# MainPDU_13VBuck.net
KiCad netlist of a schematic drawn in Altium Designer
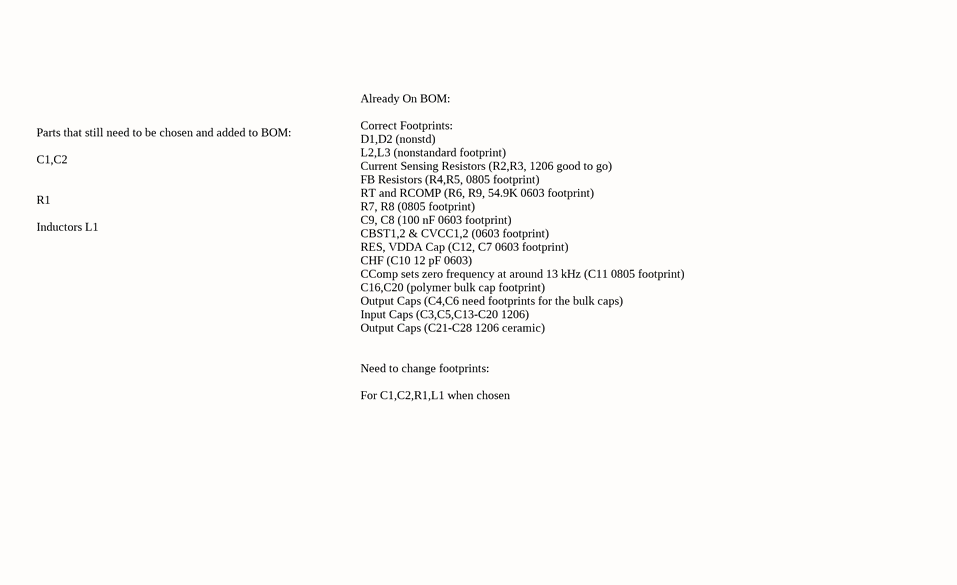
[diagram p0: MainPDU_13VBuck.SchDoc, left]
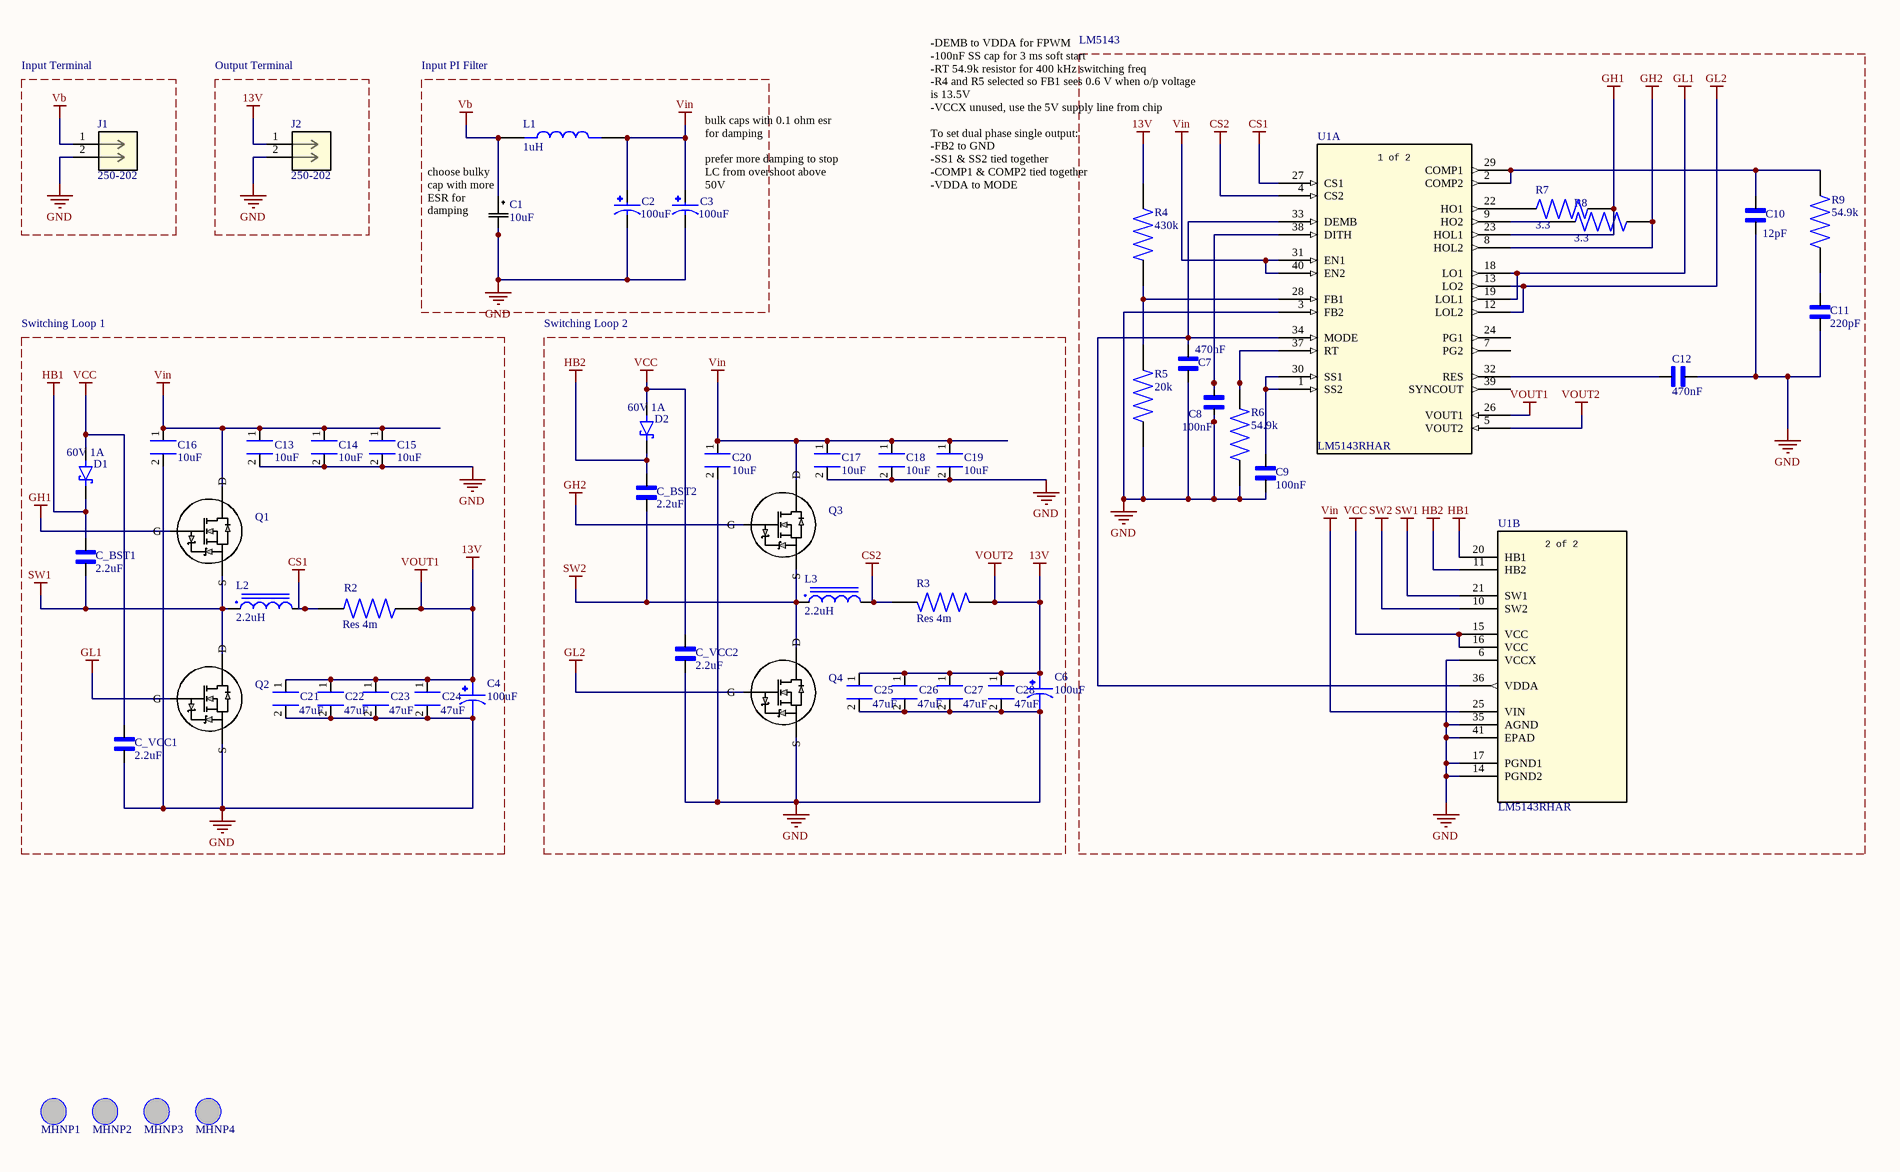
[diagram p1: MainPDU_13VBuck.SchDoc, right]

(export (version "E")
  (design (tool "Eeschema 10.0.6"))
  (components
    (comp (ref "C1")
      (value "10uF")
      (footprint "CAP_GY_6P3X5P8_NCH")
      (description "Description")
      (fields
        (field (name "MANUFACTURER_PART_NUMBER") "GYA1J100MCQ1GS")
        (field (name "COPYRIGHT") "Copyright (C) 2026 Ultra Librarian. All rights reserved.")
      )
      (libsource (lib "Schlib2") (part "GYA1J100MCQ1GS"))
    )
    (comp (ref "C2")
      (value "100uF")
      (footprint "CAP_YX_10X20_RUB")
      (description "Description")
      (fields
        (field (name "MANUFACTURER_PART_NUMBER") "100ZLH100MEFC10X20")
        (field (name "COPYRIGHT") "Copyright (C) 2025 Ultra Librarian. All rights reserved.")
      )
      (libsource (lib "Schlib2") (part "100ZLH100MEFC10X20"))
    )
    (comp (ref "C3")
      (value "100uF")
      (footprint "CAP_YX_10X20_RUB")
      (description "Description")
      (fields
        (field (name "MANUFACTURER_PART_NUMBER") "100ZLH100MEFC10X20")
        (field (name "COPYRIGHT") "Copyright (C) 2025 Ultra Librarian. All rights reserved.")
      )
      (libsource (lib "Schlib2") (part "100ZLH100MEFC10X20"))
    )
    (comp (ref "C4")
      (value "100uF")
      (footprint "CAPAE660X600N")
      (description "100 ÂµF 25 V Aluminum - Polymer Capacitors Radial, Can - SMD 36mOhm 2000 Hrs @ 125Â°C")
      (fields (field (name "MF") "KEMET") (field (name "MP") "A768EB107M1ELAS036"))
      (libsource (lib "Schlib2") (part "A768EB107M1ELAS036"))
    )
    (comp (ref "C6")
      (value "100uF")
      (footprint "CAPAE660X600N")
      (description "100 ÂµF 25 V Aluminum - Polymer Capacitors Radial, Can - SMD 36mOhm 2000 Hrs @ 125Â°C")
      (fields (field (name "MF") "KEMET") (field (name "MP") "A768EB107M1ELAS036"))
      (libsource (lib "Schlib2") (part "A768EB107M1ELAS036"))
    )
    (comp (ref "C7")
      (value "470nF")
      (footprint "CAPC1608X90N")
      (description "0.47 ÂµF Â±10% 25V Ceramic Capacitor X7R 0603 (1608 Metric)")
      (fields (field (name "MF") "Samsung Electro-Mechanics") (field (name "MP") "CL10B474KA8NFNC"))
      (libsource (lib "Schlib2") (part "CL10B474KA8NFNC"))
    )
    (comp (ref "C8")
      (value "100nF")
      (footprint "CAPC1608X90N")
      (description "0.47 ÂµF Â±10% 25V Ceramic Capacitor X7R 0603 (1608 Metric)")
      (fields (field (name "MF") "Samsung Electro-Mechanics") (field (name "MP") "CL10B474KA8NFNC"))
      (libsource (lib "Schlib2") (part "CL10B474KA8NFNC"))
    )
    (comp (ref "C9")
      (value "100nF")
      (footprint "CAPC1608X90N")
      (description "0.47 ÂµF Â±10% 25V Ceramic Capacitor X7R 0603 (1608 Metric)")
      (fields (field (name "MF") "Samsung Electro-Mechanics") (field (name "MP") "CL10B474KA8NFNC"))
      (libsource (lib "Schlib2") (part "CL10B474KA8NFNC"))
    )
    (comp (ref "C10")
      (value "12pF")
      (footprint "CAPC1608X90N")
      (description "0.47 ÂµF Â±10% 25V Ceramic Capacitor X7R 0603 (1608 Metric)")
      (fields (field (name "MF") "Samsung Electro-Mechanics") (field (name "MP") "CL10B474KA8NFNC"))
      (libsource (lib "Schlib2") (part "CL10B474KA8NFNC"))
    )
    (comp (ref "C11")
      (value "220pF")
      (footprint "CAPC2012X75N")
      (description "0805 (2012 Metric) 220 pF Â±5% 50V Ceramic Capacitor C0G, NP0")
      (fields (field (name "MF") "Samsung") (field (name "MP") "CL21C221JBANNNC"))
      (libsource (lib "Schlib2") (part "CL21C221JBANNNC"))
    )
    (comp (ref "C12")
      (value "470nF")
      (footprint "CAPC1608X90N")
      (description "0.47 ÂµF Â±10% 25V Ceramic Capacitor X7R 0603 (1608 Metric)")
      (fields (field (name "MF") "Samsung Electro-Mechanics") (field (name "MP") "CL10B474KA8NFNC"))
      (libsource (lib "") (part "CL10B474KA8NFNC_1"))
    )
    (comp (ref "C13")
      (value "10uF")
      (footprint "Cap 1206")
      (description "Generic SMD capacitor with 1206 package (3216 metric)")
      (libsource (lib "Schlib2") (part "Cap 1206"))
    )
    (comp (ref "C14")
      (value "10uF")
      (footprint "Cap 1206")
      (description "Generic SMD capacitor with 1206 package (3216 metric)")
      (libsource (lib "Schlib2") (part "Cap 1206"))
    )
    (comp (ref "C15")
      (value "10uF")
      (footprint "Cap 1206")
      (description "Generic SMD capacitor with 1206 package (3216 metric)")
      (libsource (lib "Schlib2") (part "Cap 1206"))
    )
    (comp (ref "C16")
      (value "10uF")
      (footprint "Cap 1206")
      (description "Generic SMD capacitor with 1206 package (3216 metric)")
      (libsource (lib "Schlib2") (part "Cap 1206"))
    )
    (comp (ref "C17")
      (value "10uF")
      (footprint "Cap 1206")
      (description "Generic SMD capacitor with 1206 package (3216 metric)")
      (libsource (lib "Schlib2") (part "Cap 1206"))
    )
    (comp (ref "C18")
      (value "10uF")
      (footprint "Cap 1206")
      (description "Generic SMD capacitor with 1206 package (3216 metric)")
      (libsource (lib "Schlib2") (part "Cap 1206"))
    )
    (comp (ref "C19")
      (value "10uF")
      (footprint "Cap 1206")
      (description "Generic SMD capacitor with 1206 package (3216 metric)")
      (libsource (lib "Schlib2") (part "Cap 1206"))
    )
    (comp (ref "C20")
      (value "10uF")
      (footprint "Cap 1206")
      (description "Generic SMD capacitor with 1206 package (3216 metric)")
      (libsource (lib "Schlib2") (part "Cap 1206"))
    )
    (comp (ref "C21")
      (value "47uF")
      (footprint "Cap 1206")
      (description "Generic SMD capacitor with 1206 package (3216 metric)")
      (libsource (lib "Schlib2") (part "Cap 1206"))
    )
    (comp (ref "C22")
      (value "47uF")
      (footprint "Cap 1206")
      (description "Generic SMD capacitor with 1206 package (3216 metric)")
      (libsource (lib "Schlib2") (part "Cap 1206"))
    )
    (comp (ref "C23")
      (value "47uF")
      (footprint "Cap 1206")
      (description "Generic SMD capacitor with 1206 package (3216 metric)")
      (libsource (lib "Schlib2") (part "Cap 1206"))
    )
    (comp (ref "C24")
      (value "47uF")
      (footprint "Cap 1206")
      (description "Generic SMD capacitor with 1206 package (3216 metric)")
      (libsource (lib "Schlib2") (part "Cap 1206"))
    )
    (comp (ref "C25")
      (value "47uF")
      (footprint "Cap 1206")
      (description "Generic SMD capacitor with 1206 package (3216 metric)")
      (libsource (lib "Schlib2") (part "Cap 1206"))
    )
    (comp (ref "C26")
      (value "47uF")
      (footprint "Cap 1206")
      (description "Generic SMD capacitor with 1206 package (3216 metric)")
      (libsource (lib "Schlib2") (part "Cap 1206"))
    )
    (comp (ref "C27")
      (value "47uF")
      (footprint "Cap 1206")
      (description "Generic SMD capacitor with 1206 package (3216 metric)")
      (libsource (lib "Schlib2") (part "Cap 1206"))
    )
    (comp (ref "C28")
      (value "47uF")
      (footprint "Cap 1206")
      (description "Generic SMD capacitor with 1206 package (3216 metric)")
      (libsource (lib "Schlib2") (part "Cap 1206"))
    )
    (comp (ref "C_BST1")
      (value "2.2uF")
      (footprint "CAPC1608X90N")
      (description "0.47 ÂµF Â±10% 25V Ceramic Capacitor X7R 0603 (1608 Metric)")
      (fields (field (name "MF") "Samsung Electro-Mechanics") (field (name "MP") "CL10B474KA8NFNC"))
      (libsource (lib "Schlib2") (part "CL10B474KA8NFNC"))
    )
    (comp (ref "C_BST2")
      (value "2.2uF")
      (footprint "CAPC1608X90N")
      (description "0.47 ÂµF Â±10% 25V Ceramic Capacitor X7R 0603 (1608 Metric)")
      (fields (field (name "MF") "Samsung Electro-Mechanics") (field (name "MP") "CL10B474KA8NFNC"))
      (libsource (lib "Schlib2") (part "CL10B474KA8NFNC"))
    )
    (comp (ref "C_VCC1")
      (value "2.2uF")
      (footprint "CAPC1608X90N")
      (description "0.47 ÂµF Â±10% 25V Ceramic Capacitor X7R 0603 (1608 Metric)")
      (fields (field (name "MF") "Samsung Electro-Mechanics") (field (name "MP") "CL10B474KA8NFNC"))
      (libsource (lib "Schlib2") (part "CL10B474KA8NFNC"))
    )
    (comp (ref "C_VCC2")
      (value "2.2uF")
      (footprint "CAPC1608X90N")
      (description "0.47 ÂµF Â±10% 25V Ceramic Capacitor X7R 0603 (1608 Metric)")
      (fields (field (name "MF") "Samsung Electro-Mechanics") (field (name "MP") "CL10B474KA8NFNC"))
      (libsource (lib "Schlib2") (part "CL10B474KA8NFNC"))
    )
    (comp (ref "D1")
      (value "60V 1A")
      (footprint "DIO_RB051MM_ROM")
      (description "DIODE SCHOTTKY 60V 1A PMDU")
      (fields (field (name "MP") "IDK05G120C5XTMA1") (field (name "MF") "Infineon Technologies"))
      (libsource (lib "Schlib2") (part "RBR1MM60ATR"))
    )
    (comp (ref "D2")
      (value "60V 1A")
      (footprint "DIO_RB051MM_ROM")
      (description "DIODE SCHOTTKY 60V 1A PMDU")
      (fields (field (name "MP") "IDK05G120C5XTMA1") (field (name "MF") "Infineon Technologies"))
      (libsource (lib "Schlib2") (part "RBR1MM60ATR"))
    )
    (comp (ref "J1")
      (value "250-202")
      (footprint "CONN2_250-202_WAG")
      (description "Description")
      (fields (field (name "COPYRIGHT") "Copyright (C) 2025 Ultra Librarian. All rights reserved."))
      (libsource (lib "Schlib2") (part "250-202"))
    )
    (comp (ref "J2")
      (value "250-202")
      (footprint "CONN2_250-202_WAG")
      (description "Description")
      (fields (field (name "COPYRIGHT") "Copyright (C) 2025 Ultra Librarian. All rights reserved."))
      (libsource (lib "Schlib2") (part "250-202"))
    )
    (comp (ref "L1")
      (value "1uH")
      (footprint "IND_SPM4030T-1R0M")
      (fields (field (name "MF") "{'manufacturer': u'TDK Corporation'}") (field (name "MP") "SPM4030T-1R0M"))
      (libsource (lib "Schlib2") (part "SPM4030T-1R0M"))
    )
    (comp (ref "L2")
      (value "2.2uH")
      (footprint "IND_SRU1048-2R2Y")
      (description "Ind10x10x4.8mm,2.2uH30%6.5A,shdSMD ¦ Bourns SRU1048-2R2Y")
      (fields (field (name "MF") "Bourns") (field (name "MP") "SRU1048-2R2Y"))
      (libsource (lib "Schlib2") (part "SRU1048-2R2Y"))
    )
    (comp (ref "L3")
      (value "2.2uH")
      (footprint "IND_SRU1048-2R2Y")
      (description "Ind10x10x4.8mm,2.2uH30%6.5A,shdSMD ¦ Bourns SRU1048-2R2Y")
      (fields (field (name "MF") "Bourns") (field (name "MP") "SRU1048-2R2Y"))
      (libsource (lib "Schlib2") (part "SRU1048-2R2Y"))
    )
    (comp (ref "MHNP1")
      (value "Mounting Hole Non-Plated 3.2 mm")
      (footprint "MTHNP3P2MM")
      (libsource (lib "Schlib2") (part "MTHNP3P2MM"))
    )
    (comp (ref "MHNP2")
      (value "Mounting Hole Non-Plated 3.2 mm")
      (footprint "MTHNP3P2MM")
      (libsource (lib "Schlib2") (part "MTHNP3P2MM"))
    )
    (comp (ref "MHNP3")
      (value "Mounting Hole Non-Plated 3.2 mm")
      (footprint "MTHNP3P2MM")
      (libsource (lib "Schlib2") (part "MTHNP3P2MM"))
    )
    (comp (ref "MHNP4")
      (value "Mounting Hole Non-Plated 3.2 mm")
      (footprint "MTHNP3P2MM")
      (libsource (lib "Schlib2") (part "MTHNP3P2MM"))
    )
    (comp (ref "Q1")
      (value "IRFZ44N,127")
      (footprint "SOT78_TO220_NXP")
      (description "Power Switching Mosfet")
      (fields (field (name "COPYRIGHT") "Copyright (C) 2025 Ultra Librarian. All rights reserved."))
      (libsource (lib "Schlib2") (part "IRFZ44N,127"))
    )
    (comp (ref "Q2")
      (value "IRFZ44N,127")
      (footprint "SOT78_TO220_NXP")
      (description "Power Switching Mosfet")
      (fields (field (name "COPYRIGHT") "Copyright (C) 2025 Ultra Librarian. All rights reserved."))
      (libsource (lib "Schlib2") (part "IRFZ44N,127"))
    )
    (comp (ref "Q3")
      (value "IRFZ44N,127")
      (footprint "SOT78_TO220_NXP")
      (description "Power Switching Mosfet")
      (fields (field (name "COPYRIGHT") "Copyright (C) 2025 Ultra Librarian. All rights reserved."))
      (libsource (lib "Schlib2") (part "IRFZ44N,127"))
    )
    (comp (ref "Q4")
      (value "IRFZ44N,127")
      (footprint "SOT78_TO220_NXP")
      (description "Power Switching Mosfet")
      (fields (field (name "COPYRIGHT") "Copyright (C) 2025 Ultra Librarian. All rights reserved."))
      (libsource (lib "Schlib2") (part "IRFZ44N,127"))
    )
    (comp (ref "R2")
      (value "Res 4m")
      (footprint "Res 1206")
      (description "Generic SMD resistor with 1206 package (3216 metric)")
      (libsource (lib "Schlib2") (part "Res 1206"))
    )
    (comp (ref "R3")
      (value "Res 4m")
      (footprint "Res 1206")
      (description "Generic SMD resistor with 1206 package (3216 metric)")
      (libsource (lib "Schlib2") (part "Res 1206"))
    )
    (comp (ref "R4")
      (value "430k")
      (footprint "RES0805")
      (fields (field (name "MF") "Yageo") (field (name "MP") "RC0805FR-07430KL"))
      (libsource (lib "Schlib2") (part "RC0805FR-07430KL"))
    )
    (comp (ref "R5")
      (value "20k")
      (footprint "RES0805")
      (fields (field (name "MF") "Yageo") (field (name "MP") "RC0805FR-07430KL"))
      (libsource (lib "Schlib2") (part "RC0805FR-07430KL"))
    )
    (comp (ref "R6")
      (value "54.9k")
      (footprint "RES_ERJ3EKF5492V")
      (description "Res Thick Film 0603 54.9K Ohm 1% 1/10W Â±100ppm/Â°C Molded SMD SMD Punched Carrier T/R")
      (fields (field (name "MF") "Panasonic") (field (name "MP") "ERJ3EKF5492V"))
      (libsource (lib "Schlib2") (part "ERJ3EKF5492V"))
    )
    (comp (ref "R7")
      (value "3.3")
      (footprint "RES0805")
      (fields (field (name "MF") "Yageo") (field (name "MP") "RC0805FR-07430KL"))
      (libsource (lib "Schlib2") (part "RC0805FR-07430KL"))
    )
    (comp (ref "R8")
      (value "3.3")
      (footprint "RES0805")
      (fields (field (name "MF") "Yageo") (field (name "MP") "RC0805FR-07430KL"))
      (libsource (lib "Schlib2") (part "RC0805FR-07430KL"))
    )
    (comp (ref "R9")
      (value "54.9k")
      (footprint "RES_ERJ3EKF5492V")
      (description "Res Thick Film 0603 54.9K Ohm 1% 1/10W Â±100ppm/Â°C Molded SMD SMD Punched Carrier T/R")
      (fields (field (name "MF") "Panasonic") (field (name "MP") "ERJ3EKF5492V"))
      (libsource (lib "Schlib2") (part "ERJ3EKF5492V"))
    )
    (comp (ref "U1")
      (value "LM5143RHAR")
      (footprint "VQFN40_RHA_TEX-L")
      (fields (field (name "COPYRIGHT") "Copyright (C) 2026 Ultra Librarian. All rights reserved."))
      (libsource (lib "Schlib2") (part "LM5143RHAR_1"))
    )
  )
  (nets
    (net (code "1") (name "13V") (class "Default")
      (node (ref "C21") (pin "1") (pinfunction "1_1") (pintype "passive"))
      (node (ref "C22") (pin "1") (pinfunction "1_1") (pintype "passive"))
      (node (ref "C23") (pin "1") (pinfunction "1_1") (pintype "passive"))
      (node (ref "C24") (pin "1") (pinfunction "1_1") (pintype "passive"))
      (node (ref "C25") (pin "1") (pinfunction "1_1") (pintype "passive"))
      (node (ref "C26") (pin "1") (pinfunction "1_1") (pintype "passive"))
      (node (ref "C27") (pin "1") (pinfunction "1_1") (pintype "passive"))
      (node (ref "C28") (pin "1") (pinfunction "1_1") (pintype "passive"))
      (node (ref "C4") (pin "1") (pinfunction "1_1") (pintype "passive"))
      (node (ref "C6") (pin "1") (pinfunction "1_1") (pintype "passive"))
      (node (ref "J2") (pin "1") (pinfunction "1_1") (pintype "passive"))
      (node (ref "R2") (pin "2") (pinfunction "2_2") (pintype "passive"))
      (node (ref "R3") (pin "1") (pinfunction "1_1") (pintype "passive"))
      (node (ref "R4") (pin "1") (pinfunction "1_1") (pintype "passive"))
      (node (ref "U1") (pin "26") (pinfunction "VOUT1_26") (pintype "input"))
      (node (ref "U1") (pin "5") (pinfunction "VOUT2_5") (pintype "input"))
    )
    (net (code "2") (name "CS1") (class "Default")
      (node (ref "L2") (pin "2") (pinfunction "2_2") (pintype "passive"))
      (node (ref "R2") (pin "1") (pinfunction "1_1") (pintype "passive"))
      (node (ref "U1") (pin "27") (pinfunction "CS1_27") (pintype "input"))
    )
    (net (code "3") (name "CS2") (class "Default")
      (node (ref "L3") (pin "2") (pinfunction "2_2") (pintype "passive"))
      (node (ref "R3") (pin "2") (pinfunction "2_2") (pintype "passive"))
      (node (ref "U1") (pin "4") (pinfunction "CS2_4") (pintype "input"))
    )
    (net (code "4") (name "GH1") (class "Default")
      (node (ref "Q1") (pin "1") (pinfunction "G_1") (pintype "open_collector"))
      (node (ref "R7") (pin "2") (pinfunction "2_2") (pintype "passive"))
      (node (ref "U1") (pin "23") (pinfunction "HOL1_23") (pintype "output"))
    )
    (net (code "5") (name "GH2") (class "Default")
      (node (ref "Q3") (pin "1") (pinfunction "G_1") (pintype "open_collector"))
      (node (ref "R8") (pin "2") (pinfunction "2_2") (pintype "passive"))
      (node (ref "U1") (pin "8") (pinfunction "HOL2_8") (pintype "output"))
    )
    (net (code "6") (name "GL1") (class "Default")
      (node (ref "Q2") (pin "1") (pinfunction "G_1") (pintype "open_collector"))
      (node (ref "U1") (pin "18") (pinfunction "LO1_18") (pintype "output"))
      (node (ref "U1") (pin "19") (pinfunction "LOL1_19") (pintype "output"))
    )
    (net (code "7") (name "GL2") (class "Default")
      (node (ref "Q4") (pin "1") (pinfunction "G_1") (pintype "open_collector"))
      (node (ref "U1") (pin "12") (pinfunction "LOL2_12") (pintype "output"))
      (node (ref "U1") (pin "13") (pinfunction "LO2_13") (pintype "output"))
    )
    (net (code "8") (name "GND") (class "Default")
      (node (ref "C1") (pin "2") (pinfunction "2_2") (pintype "passive"))
      (node (ref "C10") (pin "1") (pinfunction "1_1") (pintype "passive"))
      (node (ref "C11") (pin "1") (pinfunction "1_1") (pintype "passive"))
      (node (ref "C12") (pin "1") (pinfunction "1_1") (pintype "passive"))
      (node (ref "C13") (pin "2") (pinfunction "2_2") (pintype "passive"))
      (node (ref "C14") (pin "2") (pinfunction "2_2") (pintype "passive"))
      (node (ref "C15") (pin "2") (pinfunction "2_2") (pintype "passive"))
      (node (ref "C16") (pin "2") (pinfunction "2_2") (pintype "passive"))
      (node (ref "C17") (pin "2") (pinfunction "2_2") (pintype "passive"))
      (node (ref "C18") (pin "2") (pinfunction "2_2") (pintype "passive"))
      (node (ref "C19") (pin "2") (pinfunction "2_2") (pintype "passive"))
      (node (ref "C2") (pin "2") (pinfunction "2_2") (pintype "passive"))
      (node (ref "C20") (pin "2") (pinfunction "2_2") (pintype "passive"))
      (node (ref "C21") (pin "2") (pinfunction "2_2") (pintype "passive"))
      (node (ref "C22") (pin "2") (pinfunction "2_2") (pintype "passive"))
      (node (ref "C23") (pin "2") (pinfunction "2_2") (pintype "passive"))
      (node (ref "C24") (pin "2") (pinfunction "2_2") (pintype "passive"))
      (node (ref "C25") (pin "2") (pinfunction "2_2") (pintype "passive"))
      (node (ref "C26") (pin "2") (pinfunction "2_2") (pintype "passive"))
      (node (ref "C27") (pin "2") (pinfunction "2_2") (pintype "passive"))
      (node (ref "C28") (pin "2") (pinfunction "2_2") (pintype "passive"))
      (node (ref "C3") (pin "2") (pinfunction "2_2") (pintype "passive"))
      (node (ref "C4") (pin "2") (pinfunction "2_2") (pintype "passive"))
      (node (ref "C6") (pin "2") (pinfunction "2_2") (pintype "passive"))
      (node (ref "C7") (pin "1") (pinfunction "1_1") (pintype "passive"))
      (node (ref "C8") (pin "1") (pinfunction "1_1") (pintype "passive"))
      (node (ref "C9") (pin "1") (pinfunction "1_1") (pintype "passive"))
      (node (ref "C_VCC1") (pin "1") (pinfunction "1_1") (pintype "passive"))
      (node (ref "C_VCC2") (pin "1") (pinfunction "1_1") (pintype "passive"))
      (node (ref "J1") (pin "2") (pinfunction "2_2") (pintype "passive"))
      (node (ref "J2") (pin "2") (pinfunction "2_2") (pintype "passive"))
      (node (ref "Q2") (pin "3") (pinfunction "S_3") (pintype "passive"))
      (node (ref "Q4") (pin "3") (pinfunction "S_3") (pintype "passive"))
      (node (ref "R5") (pin "2") (pinfunction "2_2") (pintype "passive"))
      (node (ref "R6") (pin "2") (pinfunction "2_2") (pintype "passive"))
      (node (ref "U1") (pin "14") (pinfunction "PGND2_14") (pintype "power_in"))
      (node (ref "U1") (pin "17") (pinfunction "PGND1_17") (pintype "power_in"))
      (node (ref "U1") (pin "3") (pinfunction "FB2_3") (pintype "input"))
      (node (ref "U1") (pin "35") (pinfunction "AGND_35") (pintype "power_in"))
      (node (ref "U1") (pin "41") (pinfunction "EPAD_41") (pintype "power_in"))
      (node (ref "U1") (pin "6") (pinfunction "VCCX_6") (pintype "power_in"))
    )
    (net (code "9") (name "HB1") (class "Default")
      (node (ref "C_BST1") (pin "2") (pinfunction "2_2") (pintype "passive"))
      (node (ref "D1") (pin "1") (pinfunction "C_1") (pintype "passive"))
      (node (ref "U1") (pin "20") (pinfunction "HB1_20") (pintype "power_in"))
    )
    (net (code "10") (name "HB2") (class "Default")
      (node (ref "C_BST2") (pin "2") (pinfunction "2_2") (pintype "passive"))
      (node (ref "D2") (pin "1") (pinfunction "C_1") (pintype "passive"))
      (node (ref "U1") (pin "11") (pinfunction "HB2_11") (pintype "power_in"))
    )
    (net (code "11") (name "Net-(C11-Pad2)") (class "Default")
      (node (ref "C11") (pin "2") (pinfunction "2_2") (pintype "passive"))
      (node (ref "R9") (pin "2") (pinfunction "2_2") (pintype "passive"))
    )
    (net (code "12") (name "Net-(U1A-COMP1)") (class "Default")
      (node (ref "C10") (pin "2") (pinfunction "2_2") (pintype "passive"))
      (node (ref "R9") (pin "1") (pinfunction "1_1") (pintype "passive"))
      (node (ref "U1") (pin "2") (pinfunction "COMP2_2") (pintype "output"))
      (node (ref "U1") (pin "29") (pinfunction "COMP1_29") (pintype "output"))
    )
    (net (code "13") (name "Net-(U1A-DEMB)") (class "Default")
      (node (ref "C7") (pin "2") (pinfunction "2_2") (pintype "passive"))
      (node (ref "U1") (pin "33") (pinfunction "DEMB_33") (pintype "input"))
      (node (ref "U1") (pin "34") (pinfunction "MODE_34") (pintype "input"))
      (node (ref "U1") (pin "36") (pinfunction "VDDA_36") (pintype "output"))
    )
    (net (code "14") (name "Net-(U1A-DITH)") (class "Default")
      (node (ref "C8") (pin "2") (pinfunction "2_2") (pintype "passive"))
      (node (ref "U1") (pin "38") (pinfunction "DITH_38") (pintype "input"))
    )
    (net (code "15") (name "Net-(U1A-FB1)") (class "Default")
      (node (ref "R4") (pin "2") (pinfunction "2_2") (pintype "passive"))
      (node (ref "R5") (pin "1") (pinfunction "1_1") (pintype "passive"))
      (node (ref "U1") (pin "28") (pinfunction "FB1_28") (pintype "input"))
    )
    (net (code "16") (name "Net-(U1A-HO1)") (class "Default")
      (node (ref "R7") (pin "1") (pinfunction "1_1") (pintype "passive"))
      (node (ref "U1") (pin "22") (pinfunction "HO1_22") (pintype "output"))
    )
    (net (code "17") (name "Net-(U1A-HO2)") (class "Default")
      (node (ref "R8") (pin "1") (pinfunction "1_1") (pintype "passive"))
      (node (ref "U1") (pin "9") (pinfunction "HO2_9") (pintype "output"))
    )
    (net (code "18") (name "Net-(U1A-RES)") (class "Default")
      (node (ref "C12") (pin "2") (pinfunction "2_2") (pintype "passive"))
      (node (ref "U1") (pin "32") (pinfunction "RES_32") (pintype "output"))
    )
    (net (code "19") (name "Net-(U1A-RT)") (class "Default")
      (node (ref "R6") (pin "1") (pinfunction "1_1") (pintype "passive"))
      (node (ref "U1") (pin "37") (pinfunction "RT_37") (pintype "input"))
    )
    (net (code "20") (name "Net-(U1A-SS1)") (class "Default")
      (node (ref "C9") (pin "2") (pinfunction "2_2") (pintype "passive"))
      (node (ref "U1") (pin "1") (pinfunction "SS2_1") (pintype "input"))
      (node (ref "U1") (pin "30") (pinfunction "SS1_30") (pintype "input"))
    )
    (net (code "21") (name "SW1") (class "Default")
      (node (ref "C_BST1") (pin "1") (pinfunction "1_1") (pintype "passive"))
      (node (ref "L2") (pin "1") (pinfunction "1_1") (pintype "passive"))
      (node (ref "Q1") (pin "3") (pinfunction "S_3") (pintype "passive"))
      (node (ref "Q2") (pin "2") (pinfunction "D_2") (pintype "passive"))
      (node (ref "U1") (pin "21") (pinfunction "SW1_21") (pintype "power_in"))
    )
    (net (code "22") (name "SW2") (class "Default")
      (node (ref "C_BST2") (pin "1") (pinfunction "1_1") (pintype "passive"))
      (node (ref "L3") (pin "1") (pinfunction "1_1") (pintype "passive"))
      (node (ref "Q3") (pin "3") (pinfunction "S_3") (pintype "passive"))
      (node (ref "Q4") (pin "2") (pinfunction "D_2") (pintype "passive"))
      (node (ref "U1") (pin "10") (pinfunction "SW2_10") (pintype "power_in"))
    )
    (net (code "23") (name "VCC") (class "Default")
      (node (ref "C_VCC1") (pin "2") (pinfunction "2_2") (pintype "passive"))
      (node (ref "C_VCC2") (pin "2") (pinfunction "2_2") (pintype "passive"))
      (node (ref "D1") (pin "2") (pinfunction "A_2") (pintype "passive"))
      (node (ref "D2") (pin "2") (pinfunction "A_2") (pintype "passive"))
      (node (ref "U1") (pin "15") (pinfunction "VCC_15") (pintype "power_in"))
      (node (ref "U1") (pin "16") (pinfunction "VCC_16") (pintype "power_in"))
    )
    (net (code "24") (name "Vb") (class "Default")
      (node (ref "C1") (pin "1") (pinfunction "1_1") (pintype "passive"))
      (node (ref "J1") (pin "1") (pinfunction "1_1") (pintype "passive"))
      (node (ref "L1") (pin "1") (pinfunction "1_1") (pintype "passive"))
    )
    (net (code "25") (name "Vin") (class "Default")
      (node (ref "C13") (pin "1") (pinfunction "1_1") (pintype "passive"))
      (node (ref "C14") (pin "1") (pinfunction "1_1") (pintype "passive"))
      (node (ref "C15") (pin "1") (pinfunction "1_1") (pintype "passive"))
      (node (ref "C16") (pin "1") (pinfunction "1_1") (pintype "passive"))
      (node (ref "C17") (pin "1") (pinfunction "1_1") (pintype "passive"))
      (node (ref "C18") (pin "1") (pinfunction "1_1") (pintype "passive"))
      (node (ref "C19") (pin "1") (pinfunction "1_1") (pintype "passive"))
      (node (ref "C2") (pin "1") (pinfunction "1_1") (pintype "passive"))
      (node (ref "C20") (pin "1") (pinfunction "1_1") (pintype "passive"))
      (node (ref "C3") (pin "1") (pinfunction "1_1") (pintype "passive"))
      (node (ref "L1") (pin "2") (pinfunction "2_2") (pintype "passive"))
      (node (ref "Q1") (pin "2") (pinfunction "D_2") (pintype "passive"))
      (node (ref "Q3") (pin "2") (pinfunction "D_2") (pintype "passive"))
      (node (ref "U1") (pin "25") (pinfunction "VIN_25") (pintype "power_in"))
      (node (ref "U1") (pin "31") (pinfunction "EN1_31") (pintype "input"))
      (node (ref "U1") (pin "40") (pinfunction "EN2_40") (pintype "input"))
    )
    (net (code "26") (name "unconnected-(U1A-PG1-Pad24)") (class "Default")
      (node (ref "U1") (pin "24") (pinfunction "PG1_24") (pintype "output"))
    )
    (net (code "27") (name "unconnected-(U1A-PG2-Pad7)") (class "Default")
      (node (ref "U1") (pin "7") (pinfunction "PG2_7") (pintype "output"))
    )
    (net (code "28") (name "unconnected-(U1A-SYNCOUT-Pad39)") (class "Default")
      (node (ref "U1") (pin "39") (pinfunction "SYNCOUT_39") (pintype "output"))
    )
  )
)
